# UNG8077_EVB_7801-9031_A_5-Power.net
KiCad netlist of a schematic drawn in Altium Designer
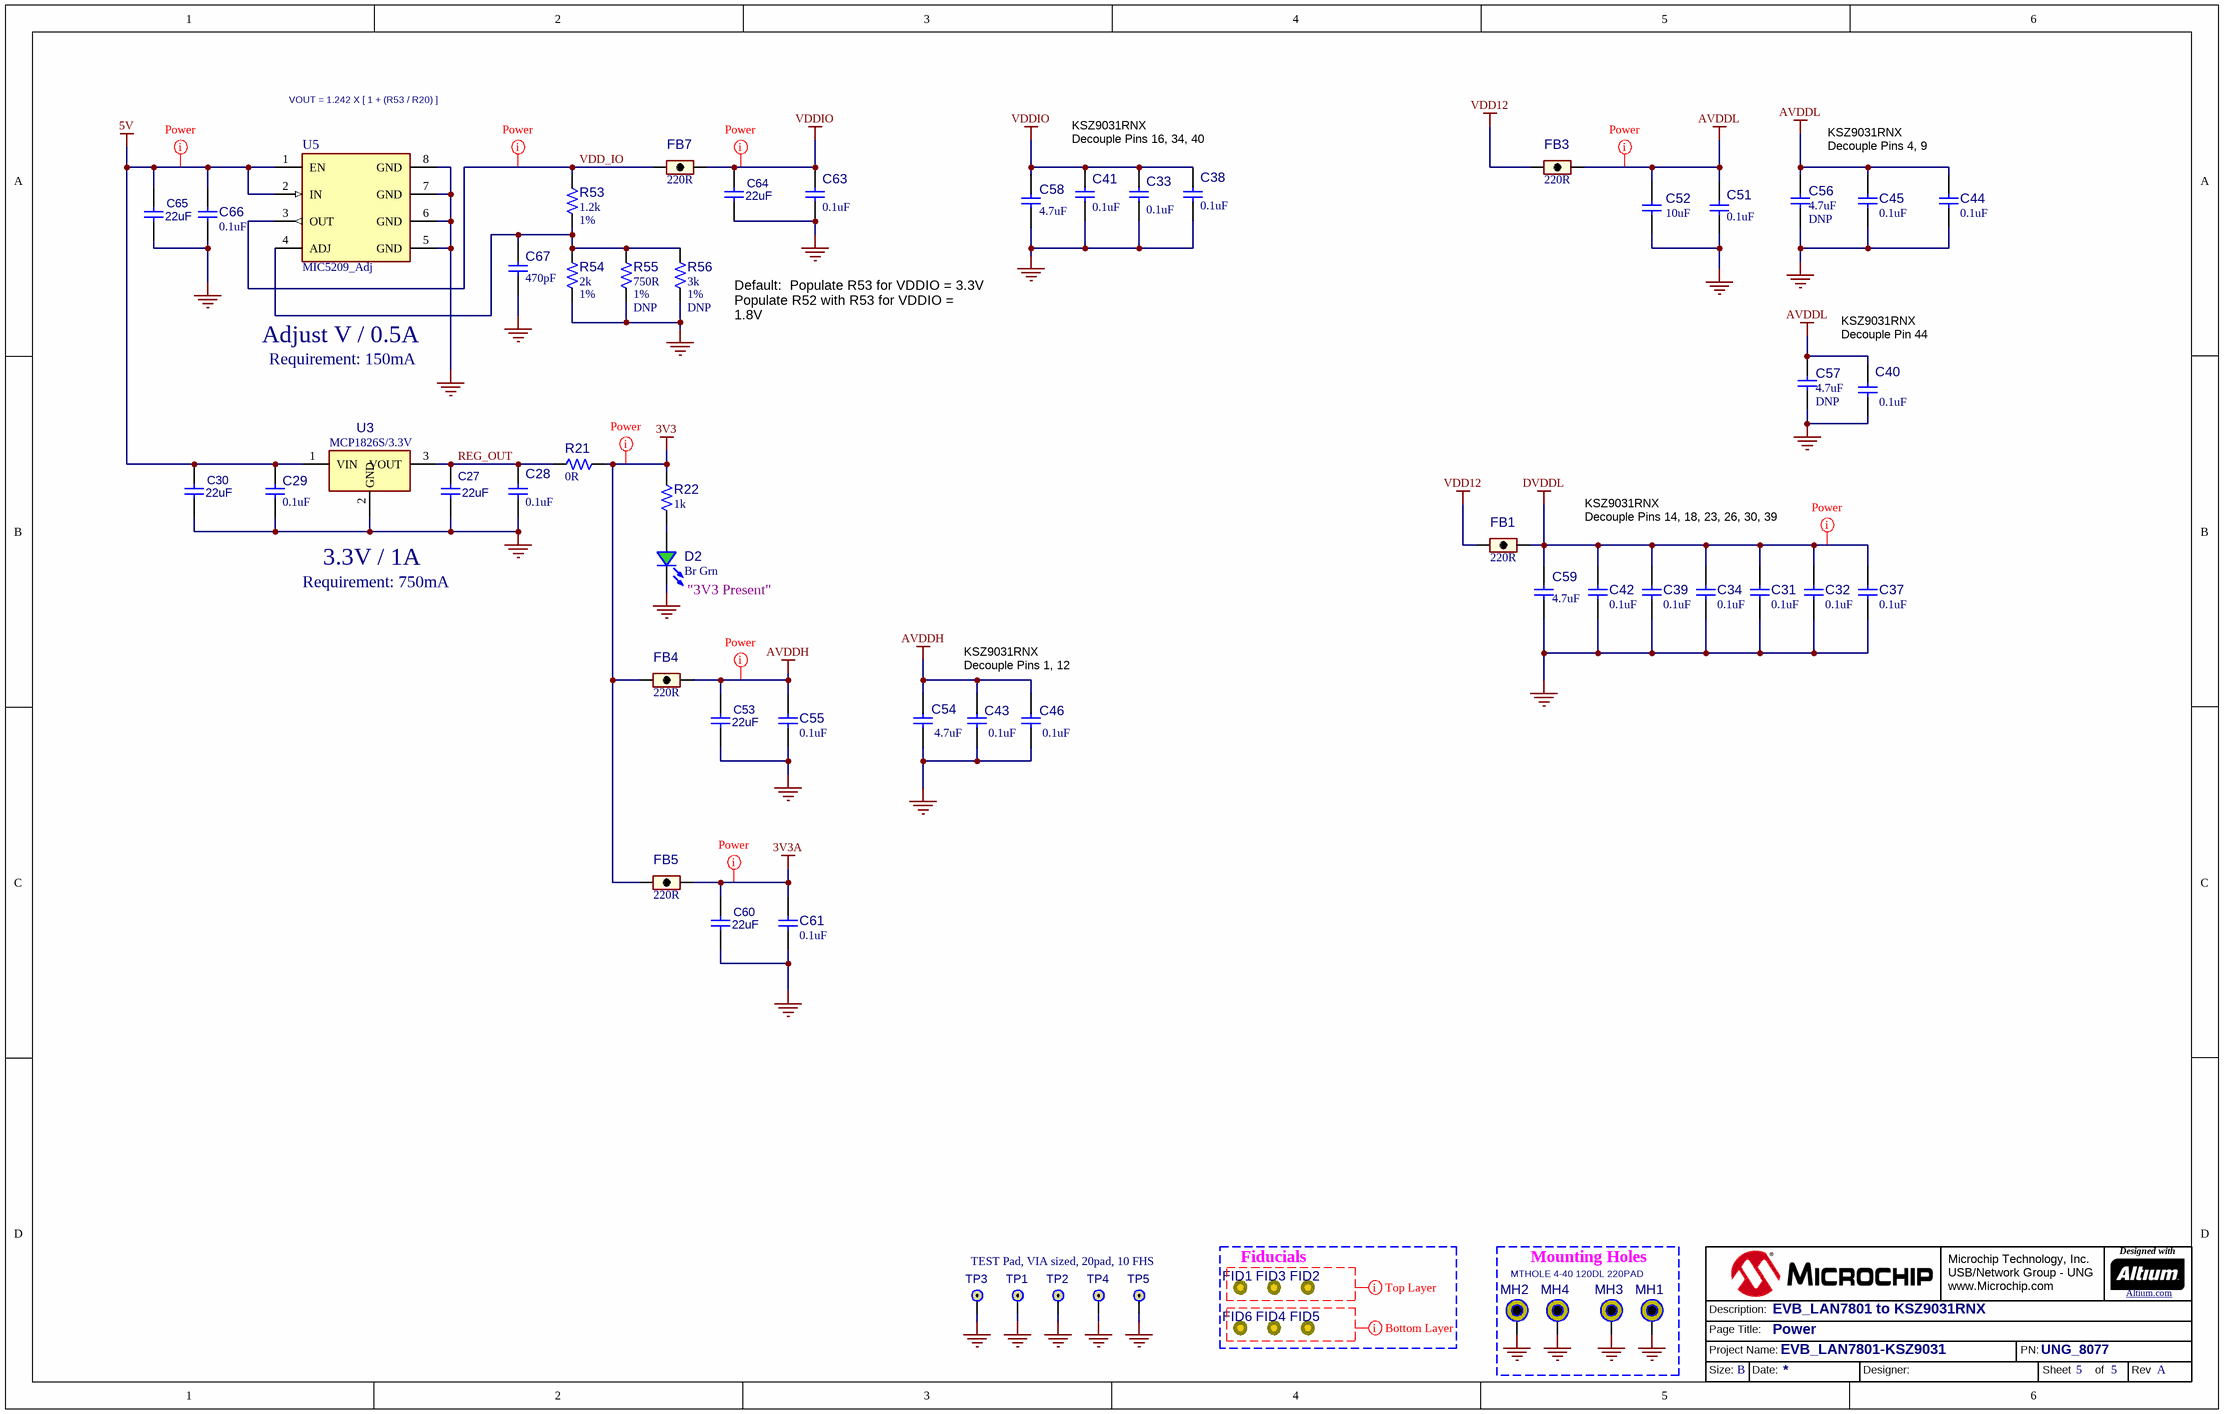
[diagram p0: UNG8077_EVB_7801-9031_A_5-Power.SchDoc]

(export (version "E")
  (design (tool "Eeschema 10.0.6"))
  (components
    (comp (ref "C27")
      (value "22uF")
      (footprint "CAP_C_0805")
      (description "CAP CER 22uF 10V 20% X5R SMD 0805")
      (fields (field (name "TOLERANCE") "20%") (field (name "OWNER") "Jennifer Hancock"))
      (libsource (lib "UNG_CAPACITORS") (part "CAP CER 22uF 10V 20% X5R SMD 0805"))
    )
    (comp (ref "C28")
      (value "0.1uF")
      (footprint "CAP_C_0402")
      (description "Capacitor")
      (fields
        (field (name "TOLERANCE") "10%")
        (field (name "Comment") "CAP CER 0.1UF 35V")
        (field (name "OWNER") "Jamus Griego")
      )
      (libsource (lib "MCHP-CDB-Offline") (part "Capacitor NP"))
    )
    (comp (ref "C29")
      (value "0.1uF")
      (footprint "CAP_C_0402")
      (description "Capacitor")
      (fields
        (field (name "TOLERANCE") "10%")
        (field (name "Comment") "CAP CER 0.1UF 35V")
        (field (name "OWNER") "Jamus Griego")
      )
      (libsource (lib "MCHP-CDB-Offline") (part "Capacitor NP"))
    )
    (comp (ref "C30")
      (value "22uF")
      (footprint "CAP_C_0805")
      (description "CAP CER 22uF 10V 20% X5R SMD 0805")
      (fields (field (name "TOLERANCE") "20%") (field (name "OWNER") "Jennifer Hancock"))
      (libsource (lib "UNG_CAPACITORS") (part "CAP CER 22uF 10V 20% X5R SMD 0805"))
    )
    (comp (ref "C31")
      (value "0.1uF")
      (footprint "CAP_C_0402")
      (description "Capacitor")
      (fields
        (field (name "TOLERANCE") "10%")
        (field (name "Comment") "CAP CER 0.1UF 35V")
        (field (name "OWNER") "Jamus Griego")
      )
      (libsource (lib "MCHP-CDB-Offline") (part "Capacitor NP"))
    )
    (comp (ref "C32")
      (value "0.1uF")
      (footprint "CAP_C_0402")
      (description "Capacitor")
      (fields
        (field (name "TOLERANCE") "10%")
        (field (name "Comment") "CAP CER 0.1UF 35V")
        (field (name "OWNER") "Jamus Griego")
      )
      (libsource (lib "MCHP-CDB-Offline") (part "Capacitor NP"))
    )
    (comp (ref "C33")
      (value "0.1uF")
      (footprint "CAP_C_0402")
      (description "Capacitor")
      (fields
        (field (name "TOLERANCE") "10%")
        (field (name "Comment") "CAP CER 0.1UF 35V")
        (field (name "OWNER") "Jamus Griego")
      )
      (libsource (lib "MCHP-CDB-Offline") (part "Capacitor NP"))
    )
    (comp (ref "C34")
      (value "0.1uF")
      (footprint "CAP_C_0402")
      (description "Capacitor")
      (fields
        (field (name "TOLERANCE") "10%")
        (field (name "Comment") "CAP CER 0.1UF 35V")
        (field (name "OWNER") "Jamus Griego")
      )
      (libsource (lib "MCHP-CDB-Offline") (part "Capacitor NP"))
    )
    (comp (ref "C37")
      (value "0.1uF")
      (footprint "CAP_C_0402")
      (description "Capacitor")
      (fields
        (field (name "TOLERANCE") "10%")
        (field (name "Comment") "CAP CER 0.1UF 35V")
        (field (name "OWNER") "Jamus Griego")
      )
      (libsource (lib "MCHP-CDB-Offline") (part "Capacitor NP"))
    )
    (comp (ref "C38")
      (value "0.1uF")
      (footprint "CAP_C_0402")
      (description "Capacitor")
      (fields
        (field (name "TOLERANCE") "10%")
        (field (name "Comment") "CAP CER 0.1UF 35V")
        (field (name "OWNER") "Jamus Griego")
      )
      (libsource (lib "MCHP-CDB-Offline") (part "Capacitor NP"))
    )
    (comp (ref "C39")
      (value "0.1uF")
      (footprint "CAP_C_0402")
      (description "Capacitor")
      (fields
        (field (name "TOLERANCE") "10%")
        (field (name "Comment") "CAP CER 0.1UF 35V")
        (field (name "OWNER") "Jamus Griego")
      )
      (libsource (lib "MCHP-CDB-Offline") (part "Capacitor NP"))
    )
    (comp (ref "C40")
      (value "0.1uF")
      (footprint "CAP_C_0402")
      (description "Capacitor")
      (fields
        (field (name "TOLERANCE") "10%")
        (field (name "Comment") "CAP CER 0.1UF 35V")
        (field (name "OWNER") "Jamus Griego")
      )
      (libsource (lib "MCHP-CDB-Offline") (part "Capacitor NP"))
    )
    (comp (ref "C41")
      (value "0.1uF")
      (footprint "CAP_C_0402")
      (description "Capacitor")
      (fields
        (field (name "TOLERANCE") "10%")
        (field (name "Comment") "CAP CER 0.1UF 35V")
        (field (name "OWNER") "Jamus Griego")
      )
      (libsource (lib "MCHP-CDB-Offline") (part "Capacitor NP"))
    )
    (comp (ref "C42")
      (value "0.1uF")
      (footprint "CAP_C_0402")
      (description "Capacitor")
      (fields
        (field (name "TOLERANCE") "10%")
        (field (name "Comment") "CAP CER 0.1UF 35V")
        (field (name "OWNER") "Jamus Griego")
      )
      (libsource (lib "MCHP-CDB-Offline") (part "Capacitor NP"))
    )
    (comp (ref "C43")
      (value "0.1uF")
      (footprint "CAP_C_0402")
      (description "Capacitor")
      (fields
        (field (name "TOLERANCE") "10%")
        (field (name "Comment") "CAP CER 0.1UF 35V")
        (field (name "OWNER") "Jamus Griego")
      )
      (libsource (lib "MCHP-CDB-Offline") (part "Capacitor NP"))
    )
    (comp (ref "C44")
      (value "0.1uF")
      (footprint "CAP_C_0402")
      (description "Capacitor")
      (fields
        (field (name "TOLERANCE") "10%")
        (field (name "Comment") "CAP CER 0.1UF 35V")
        (field (name "OWNER") "Jamus Griego")
      )
      (libsource (lib "MCHP-CDB-Offline") (part "Capacitor NP"))
    )
    (comp (ref "C45")
      (value "0.1uF")
      (footprint "CAP_C_0402")
      (description "Capacitor")
      (fields
        (field (name "TOLERANCE") "10%")
        (field (name "Comment") "CAP CER 0.1UF 35V")
        (field (name "OWNER") "Jamus Griego")
      )
      (libsource (lib "MCHP-CDB-Offline") (part "Capacitor NP"))
    )
    (comp (ref "C46")
      (value "0.1uF")
      (footprint "CAP_C_0402")
      (description "Capacitor")
      (fields
        (field (name "TOLERANCE") "10%")
        (field (name "Comment") "CAP CER 0.1UF 35V")
        (field (name "OWNER") "Jamus Griego")
      )
      (libsource (lib "MCHP-CDB-Offline") (part "Capacitor NP"))
    )
    (comp (ref "C51")
      (value "0.1uF")
      (footprint "CAP_C_0402")
      (description "Capacitor")
      (fields
        (field (name "TOLERANCE") "10%")
        (field (name "Comment") "CAP CER 0.1UF 35V")
        (field (name "OWNER") "Jamus Griego")
      )
      (libsource (lib "MCHP-CDB-Offline") (part "Capacitor NP"))
    )
    (comp (ref "C52")
      (value "10uF")
      (footprint "CAP_C_0603")
      (description "Capacitor")
      (fields (field (name "TOLERANCE") "20%") (field (name "Comment") "Capacitor NP"))
      (libsource (lib "MCHP-CDB-Offline") (part "Capacitor NP"))
    )
    (comp (ref "C53")
      (value "22uF")
      (footprint "CAP_C_0805")
      (description "CAP CER 22uF 10V 20% X5R SMD 0805")
      (fields (field (name "TOLERANCE") "20%") (field (name "OWNER") "Jennifer Hancock"))
      (libsource (lib "UNG_CAPACITORS") (part "CAP CER 22uF 10V 20% X5R SMD 0805"))
    )
    (comp (ref "C54")
      (value "4.7uF")
      (footprint "CAP_C_0603")
      (description "Capacitor")
      (fields (field (name "TOLERANCE") "20%") (field (name "Comment") "Capacitor NP"))
      (libsource (lib "MCHP-CDB-Offline") (part "Capacitor NP"))
    )
    (comp (ref "C55")
      (value "0.1uF")
      (footprint "CAP_C_0402")
      (description "Capacitor")
      (fields
        (field (name "TOLERANCE") "10%")
        (field (name "Comment") "CAP CER 0.1UF 35V")
        (field (name "OWNER") "Jamus Griego")
      )
      (libsource (lib "MCHP-CDB-Offline") (part "Capacitor NP"))
    )
    (comp (ref "C56")
      (value "4.7uF")
      (footprint "CAP_C_0603")
      (description "Capacitor")
      (fields
        (field (name "TOLERANCE") "20%")
        (field (name "POPULATED") "DNP")
        (field (name "Comment") "Capacitor NP")
      )
      (libsource (lib "MCHP-CDB-Offline") (part "Capacitor NP"))
    )
    (comp (ref "C57")
      (value "4.7uF")
      (footprint "CAP_C_0603")
      (description "Capacitor")
      (fields
        (field (name "TOLERANCE") "20%")
        (field (name "POPULATED") "DNP")
        (field (name "Comment") "Capacitor NP")
      )
      (libsource (lib "MCHP-CDB-Offline") (part "Capacitor NP"))
    )
    (comp (ref "C58")
      (value "4.7uF")
      (footprint "CAP_C_0603")
      (description "Capacitor")
      (fields (field (name "TOLERANCE") "20%") (field (name "Comment") "Capacitor NP"))
      (libsource (lib "MCHP-CDB-Offline") (part "Capacitor NP"))
    )
    (comp (ref "C59")
      (value "4.7uF")
      (footprint "CAP_C_0603")
      (description "Capacitor")
      (fields (field (name "TOLERANCE") "20%") (field (name "Comment") "Capacitor NP"))
      (libsource (lib "MCHP-CDB-Offline") (part "Capacitor NP"))
    )
    (comp (ref "C60")
      (value "22uF")
      (footprint "CAP_C_0805")
      (description "CAP CER 22uF 10V 20% X5R SMD 0805")
      (fields (field (name "TOLERANCE") "20%") (field (name "OWNER") "Jennifer Hancock"))
      (libsource (lib "UNG_CAPACITORS") (part "CAP CER 22uF 10V 20% X5R SMD 0805"))
    )
    (comp (ref "C61")
      (value "0.1uF")
      (footprint "CAP_C_0402")
      (description "Capacitor")
      (fields
        (field (name "TOLERANCE") "10%")
        (field (name "Comment") "CAP CER 0.1UF 35V")
        (field (name "OWNER") "Jamus Griego")
      )
      (libsource (lib "MCHP-CDB-Offline") (part "Capacitor NP"))
    )
    (comp (ref "C63")
      (value "0.1uF")
      (footprint "CAP_C_0402")
      (description "Capacitor")
      (fields
        (field (name "TOLERANCE") "10%")
        (field (name "Comment") "CAP CER 0.1UF 35V")
        (field (name "OWNER") "Jamus Griego")
      )
      (libsource (lib "MCHP-CDB-Offline") (part "Capacitor NP"))
    )
    (comp (ref "C64")
      (value "22uF")
      (footprint "CAP_C_0805")
      (description "CAP CER 22uF 10V 20% X5R SMD 0805")
      (fields (field (name "TOLERANCE") "20%") (field (name "OWNER") "Jennifer Hancock"))
      (libsource (lib "UNG_CAPACITORS") (part "CAP CER 22uF 10V 20% X5R SMD 0805"))
    )
    (comp (ref "C65")
      (value "22uF")
      (footprint "CAP_C_0805")
      (description "CAP CER 22uF 10V 20% X5R SMD 0805")
      (fields (field (name "TOLERANCE") "20%") (field (name "OWNER") "Jennifer Hancock"))
      (libsource (lib "UNG_CAPACITORS") (part "CAP CER 22uF 10V 20% X5R SMD 0805"))
    )
    (comp (ref "C66")
      (value "0.1uF")
      (footprint "CAP_C_0402")
      (description "Capacitor")
      (fields
        (field (name "TOLERANCE") "10%")
        (field (name "Comment") "CAP CER 0.1UF 35V")
        (field (name "OWNER") "Jamus Griego")
      )
      (libsource (lib "MCHP-CDB-Offline") (part "Capacitor NP"))
    )
    (comp (ref "C67")
      (value "470pF")
      (footprint "CAP_C_0402")
      (description "Capacitor")
      (fields
        (field (name "TOLERANCE") "5%")
        (field (name "Comment") "Capacitor NP")
        (field (name "OWNER") "Duane Burt")
      )
      (libsource (lib "MCHP-CDB-Offline") (part "Capacitor NP"))
    )
    (comp (ref "D2")
      (value "Br Grn")
      (footprint "LED_0603_GREEN")
      (description "LED, Bright Green, 0603")
      (fields (field (name "Comment") "LED") (field (name "OWNER") "Jennifer Hancock"))
      (libsource (lib "UNG_DIODES") (part "LED, Bright Green, 0603"))
    )
    (comp (ref "FB1")
      (value "220R")
      (footprint "IND_C_0603")
      (fields (field (name "Comment") "Ferrite Bead") (field (name "OWNER") "Razvan Cristescu"))
      (libsource (lib "MCHP-CDB-Offline") (part "Ferrite Bead"))
    )
    (comp (ref "FB3")
      (value "220R")
      (footprint "IND_C_0603")
      (fields (field (name "Comment") "Ferrite Bead") (field (name "OWNER") "Razvan Cristescu"))
      (libsource (lib "MCHP-CDB-Offline") (part "Ferrite Bead"))
    )
    (comp (ref "FB4")
      (value "220R")
      (footprint "IND_C_0603")
      (fields (field (name "Comment") "Ferrite Bead") (field (name "OWNER") "Razvan Cristescu"))
      (libsource (lib "MCHP-CDB-Offline") (part "Ferrite Bead"))
    )
    (comp (ref "FB5")
      (value "220R")
      (footprint "IND_C_0603")
      (fields (field (name "Comment") "Ferrite Bead") (field (name "OWNER") "Razvan Cristescu"))
      (libsource (lib "MCHP-CDB-Offline") (part "Ferrite Bead"))
    )
    (comp (ref "FB7")
      (value "220R")
      (footprint "IND_C_0603")
      (fields (field (name "Comment") "Ferrite Bead") (field (name "OWNER") "Razvan Cristescu"))
      (libsource (lib "MCHP-CDB-Offline") (part "Ferrite Bead"))
    )
    (comp (ref "FID1")
      (value "FIDUCIAL")
      (footprint "FIDUCIAL")
      (libsource (lib "UNG_MISC") (part "FIDUCIAL"))
    )
    (comp (ref "FID2")
      (value "FIDUCIAL")
      (footprint "FIDUCIAL")
      (libsource (lib "UNG_MISC") (part "FIDUCIAL"))
    )
    (comp (ref "FID3")
      (value "FIDUCIAL")
      (footprint "FIDUCIAL")
      (libsource (lib "UNG_MISC") (part "FIDUCIAL"))
    )
    (comp (ref "FID4")
      (value "FIDUCIAL")
      (footprint "FIDUCIAL")
      (libsource (lib "UNG_MISC") (part "FIDUCIAL"))
    )
    (comp (ref "FID5")
      (value "FIDUCIAL")
      (footprint "FIDUCIAL")
      (libsource (lib "UNG_MISC") (part "FIDUCIAL"))
    )
    (comp (ref "FID6")
      (value "FIDUCIAL")
      (footprint "FIDUCIAL")
      (libsource (lib "UNG_MISC") (part "FIDUCIAL"))
    )
    (comp (ref "MH1")
      (value "MTHOLE 4-40 120DL 220PAD")
      (footprint "MTHOLE_4-40")
      (libsource (lib "UNG_MISC") (part "MTHOLE 4-40 120DL 220PAD"))
    )
    (comp (ref "MH2")
      (value "MTHOLE 4-40 120DL 220PAD")
      (footprint "MTHOLE_4-40")
      (libsource (lib "UNG_MISC") (part "MTHOLE 4-40 120DL 220PAD"))
    )
    (comp (ref "MH3")
      (value "MTHOLE 4-40 120DL 220PAD")
      (footprint "MTHOLE_4-40")
      (libsource (lib "UNG_MISC") (part "MTHOLE 4-40 120DL 220PAD"))
    )
    (comp (ref "MH4")
      (value "MTHOLE 4-40 120DL 220PAD")
      (footprint "MTHOLE_4-40")
      (libsource (lib "UNG_MISC") (part "MTHOLE 4-40 120DL 220PAD"))
    )
    (comp (ref "R21")
      (value "0R")
      (footprint "RES_C_0603")
      (description "Resistor")
      (fields (field (name "POWER") "1/10W"))
      (libsource (lib "MCHP-CDB-Offline") (part "Resistor"))
    )
    (comp (ref "R22")
      (value "1k")
      (footprint "RES_C_0603")
      (description "Resistor")
      (fields (field (name "TOLERANCE") "1%") (field (name "VOLTAGE") "75V"))
      (libsource (lib "MCHP-CDB") (part "Resistor"))
    )
    (comp (ref "R53")
      (value "1.2k")
      (footprint "RES_C_0603")
      (description "Resistor")
      (fields
        (field (name "TOLERANCE") "1%")
        (field (name "VOLTAGE") "50V")
        (field (name "POWER") "1/10W")
        (field (name "OWNER") "Aaron VanDuerm")
      )
      (libsource (lib "MCHP-CDB-Offline") (part "Resistor"))
    )
    (comp (ref "R54")
      (value "2k")
      (footprint "RES_C_0603")
      (description "Resistor")
      (fields (field (name "TOLERANCE") "1%") (field (name "VOLTAGE") "75V") (field (name "POWER") "1/10W"))
      (libsource (lib "MCHP-CDB-Offline") (part "Resistor"))
    )
    (comp (ref "R55")
      (value "750R")
      (footprint "RES_C_0603")
      (description "Resistor")
      (fields
        (field (name "TOLERANCE") "1%")
        (field (name "VOLTAGE") "75V")
        (field (name "POWER") "1/10W")
        (field (name "POPULATED") "DNP")
        (field (name "OWNER") "Tad Ahlvers")
      )
      (libsource (lib "MCHP-CDB-Offline") (part "Resistor"))
    )
    (comp (ref "R56")
      (value "3k")
      (footprint "RES_C_0603")
      (description "Resistor")
      (fields
        (field (name "TOLERANCE") "1%")
        (field (name "VOLTAGE") "75V")
        (field (name "POWER") "1/10W")
        (field (name "POPULATED") "DNP")
        (field (name "OWNER") "Bogdan P (M91398)")
      )
      (libsource (lib "MCHP-CDB-Offline") (part "Resistor"))
    )
    (comp (ref "TP1")
      (value "Jumper")
      (footprint "TP_PAD_VIA_20-10")
      (description "Test Pad TH VIA 20X10")
      (fields (field (name "MANUFACTURER PART NUMBER") "none"))
      (libsource (lib "UNG_CONNECTORS") (part "TEST PAD TH VIA 20X10"))
    )
    (comp (ref "TP2")
      (value "Jumper")
      (footprint "TP_PAD_VIA_20-10")
      (description "Test Pad TH VIA 20X10")
      (fields (field (name "MANUFACTURER PART NUMBER") "none"))
      (libsource (lib "UNG_CONNECTORS") (part "TEST PAD TH VIA 20X10"))
    )
    (comp (ref "TP3")
      (value "Jumper")
      (footprint "TP_PAD_VIA_20-10")
      (description "Test Pad TH VIA 20X10")
      (fields (field (name "MANUFACTURER PART NUMBER") "none"))
      (libsource (lib "UNG_CONNECTORS") (part "TEST PAD TH VIA 20X10"))
    )
    (comp (ref "TP4")
      (value "Jumper")
      (footprint "TP_PAD_VIA_20-10")
      (description "Test Pad TH VIA 20X10")
      (fields (field (name "MANUFACTURER PART NUMBER") "none"))
      (libsource (lib "UNG_CONNECTORS") (part "TEST PAD TH VIA 20X10"))
    )
    (comp (ref "TP5")
      (value "Jumper")
      (footprint "TP_PAD_VIA_20-10")
      (description "Test Pad TH VIA 20X10")
      (fields
        (field (name "MANUFACTURER PART NUMBER") "none")
        (field (name "DESCRIPTION_") "TEST Pad, VIA sized, 20pad, 10 FHS")
      )
      (libsource (lib "UNG_CONNECTORS") (part "TEST PAD TH VIA 20X10"))
    )
    (comp (ref "U3")
      (value "MCP1826S/3.3V")
      (footprint "SOT-223-3")
      (description "LDO")
      (fields
        (field (name "Comment") "MCP182XS SOT-223-3_DDPAK-3_TO-220-3")
        (field (name "OWNER") "Aaron VanDuerm")
      )
      (libsource (lib "MCHP-CDB-Offline") (part "MCP182XS SOT-223-3_DDPAK-3_TO-220-3"))
    )
    (comp (ref "U5")
      (value "MIC5209_Adj")
      (footprint "SOIC-8")
      (description "LDO MIC5209")
      (fields (field (name "Comment") "MIC5209 ADJ SOIC-8"))
      (libsource (lib "MCHP-CDB") (part "MIC5209 ADJ SOIC-8"))
    )
  )
  (nets
    (net (code "1") (name "/REG_OUT") (class "Default")
      (node (ref "C27") (pin "2") (pinfunction "2_2") (pintype "passive"))
      (node (ref "C28") (pin "2") (pinfunction "2_2") (pintype "passive"))
      (node (ref "R21") (pin "1") (pinfunction "1_1") (pintype "passive"))
      (node (ref "U3") (pin "3") (pinfunction "VOUT_3") (pintype "power_in"))
    )
    (net (code "2") (name "/VDD_IO") (class "Default")
      (node (ref "FB7") (pin "1") (pinfunction "1_1") (pintype "passive"))
      (node (ref "R53") (pin "2") (pinfunction "2_2") (pintype "passive"))
      (node (ref "U5") (pin "3") (pinfunction "OUT_3") (pintype "output"))
    )
    (net (code "3") (name "3V3") (class "Default")
      (node (ref "FB4") (pin "1") (pinfunction "1_1") (pintype "passive"))
      (node (ref "FB5") (pin "1") (pinfunction "1_1") (pintype "passive"))
      (node (ref "R21") (pin "2") (pinfunction "2_2") (pintype "passive"))
      (node (ref "R22") (pin "1") (pinfunction "1_1") (pintype "passive"))
    )
    (net (code "4") (name "3V3A") (class "Default")
      (node (ref "C60") (pin "2") (pinfunction "2_2") (pintype "passive"))
      (node (ref "C61") (pin "2") (pinfunction "2_2") (pintype "passive"))
      (node (ref "FB5") (pin "2") (pinfunction "2_2") (pintype "passive"))
    )
    (net (code "5") (name "5V") (class "Default")
      (node (ref "C29") (pin "2") (pinfunction "2_2") (pintype "passive"))
      (node (ref "C30") (pin "2") (pinfunction "2_2") (pintype "passive"))
      (node (ref "C65") (pin "2") (pinfunction "2_2") (pintype "passive"))
      (node (ref "C66") (pin "2") (pinfunction "2_2") (pintype "passive"))
      (node (ref "U3") (pin "1") (pinfunction "VIN_1") (pintype "power_in"))
      (node (ref "U5") (pin "1") (pinfunction "EN_1") (pintype "passive"))
      (node (ref "U5") (pin "2") (pinfunction "IN_2") (pintype "input"))
    )
    (net (code "6") (name "AVDDH") (class "Default")
      (node (ref "C43") (pin "2") (pinfunction "2_2") (pintype "passive"))
      (node (ref "C46") (pin "2") (pinfunction "2_2") (pintype "passive"))
      (node (ref "C53") (pin "2") (pinfunction "2_2") (pintype "passive"))
      (node (ref "C54") (pin "2") (pinfunction "2_2") (pintype "passive"))
      (node (ref "C55") (pin "2") (pinfunction "2_2") (pintype "passive"))
      (node (ref "FB4") (pin "2") (pinfunction "2_2") (pintype "passive"))
    )
    (net (code "7") (name "AVDDL") (class "Default")
      (node (ref "C40") (pin "2") (pinfunction "2_2") (pintype "passive"))
      (node (ref "C44") (pin "2") (pinfunction "2_2") (pintype "passive"))
      (node (ref "C45") (pin "2") (pinfunction "2_2") (pintype "passive"))
      (node (ref "C51") (pin "2") (pinfunction "2_2") (pintype "passive"))
      (node (ref "C52") (pin "2") (pinfunction "2_2") (pintype "passive"))
      (node (ref "C56") (pin "2") (pinfunction "2_2") (pintype "passive"))
      (node (ref "C57") (pin "2") (pinfunction "2_2") (pintype "passive"))
      (node (ref "FB3") (pin "2") (pinfunction "2_2") (pintype "passive"))
    )
    (net (code "8") (name "DVDDL") (class "Default")
      (node (ref "C31") (pin "2") (pinfunction "2_2") (pintype "passive"))
      (node (ref "C32") (pin "2") (pinfunction "2_2") (pintype "passive"))
      (node (ref "C34") (pin "2") (pinfunction "2_2") (pintype "passive"))
      (node (ref "C37") (pin "2") (pinfunction "2_2") (pintype "passive"))
      (node (ref "C39") (pin "2") (pinfunction "2_2") (pintype "passive"))
      (node (ref "C42") (pin "2") (pinfunction "2_2") (pintype "passive"))
      (node (ref "C59") (pin "2") (pinfunction "2_2") (pintype "passive"))
      (node (ref "FB1") (pin "2") (pinfunction "2_2") (pintype "passive"))
    )
    (net (code "9") (name "GND") (class "Default")
      (node (ref "C27") (pin "1") (pinfunction "1_1") (pintype "passive"))
      (node (ref "C28") (pin "1") (pinfunction "1_1") (pintype "passive"))
      (node (ref "C29") (pin "1") (pinfunction "1_1") (pintype "passive"))
      (node (ref "C30") (pin "1") (pinfunction "1_1") (pintype "passive"))
      (node (ref "C31") (pin "1") (pinfunction "1_1") (pintype "passive"))
      (node (ref "C32") (pin "1") (pinfunction "1_1") (pintype "passive"))
      (node (ref "C33") (pin "1") (pinfunction "1_1") (pintype "passive"))
      (node (ref "C34") (pin "1") (pinfunction "1_1") (pintype "passive"))
      (node (ref "C37") (pin "1") (pinfunction "1_1") (pintype "passive"))
      (node (ref "C38") (pin "1") (pinfunction "1_1") (pintype "passive"))
      (node (ref "C39") (pin "1") (pinfunction "1_1") (pintype "passive"))
      (node (ref "C40") (pin "1") (pinfunction "1_1") (pintype "passive"))
      (node (ref "C41") (pin "1") (pinfunction "1_1") (pintype "passive"))
      (node (ref "C42") (pin "1") (pinfunction "1_1") (pintype "passive"))
      (node (ref "C43") (pin "1") (pinfunction "1_1") (pintype "passive"))
      (node (ref "C44") (pin "1") (pinfunction "1_1") (pintype "passive"))
      (node (ref "C45") (pin "1") (pinfunction "1_1") (pintype "passive"))
      (node (ref "C46") (pin "1") (pinfunction "1_1") (pintype "passive"))
      (node (ref "C51") (pin "1") (pinfunction "1_1") (pintype "passive"))
      (node (ref "C52") (pin "1") (pinfunction "1_1") (pintype "passive"))
      (node (ref "C53") (pin "1") (pinfunction "1_1") (pintype "passive"))
      (node (ref "C54") (pin "1") (pinfunction "1_1") (pintype "passive"))
      (node (ref "C55") (pin "1") (pinfunction "1_1") (pintype "passive"))
      (node (ref "C56") (pin "1") (pinfunction "1_1") (pintype "passive"))
      (node (ref "C57") (pin "1") (pinfunction "1_1") (pintype "passive"))
      (node (ref "C58") (pin "1") (pinfunction "1_1") (pintype "passive"))
      (node (ref "C59") (pin "1") (pinfunction "1_1") (pintype "passive"))
      (node (ref "C60") (pin "1") (pinfunction "1_1") (pintype "passive"))
      (node (ref "C61") (pin "1") (pinfunction "1_1") (pintype "passive"))
      (node (ref "C63") (pin "1") (pinfunction "1_1") (pintype "passive"))
      (node (ref "C64") (pin "1") (pinfunction "1_1") (pintype "passive"))
      (node (ref "C65") (pin "1") (pinfunction "1_1") (pintype "passive"))
      (node (ref "C66") (pin "1") (pinfunction "1_1") (pintype "passive"))
      (node (ref "C67") (pin "1") (pinfunction "1_1") (pintype "passive"))
      (node (ref "D2") (pin "2") (pinfunction "K_2") (pintype "passive"))
      (node (ref "MH1") (pin "1") (pinfunction "1_1") (pintype "passive"))
      (node (ref "MH2") (pin "1") (pinfunction "1_1") (pintype "passive"))
      (node (ref "MH3") (pin "1") (pinfunction "1_1") (pintype "passive"))
      (node (ref "MH4") (pin "1") (pinfunction "1_1") (pintype "passive"))
      (node (ref "R54") (pin "1") (pinfunction "1_1") (pintype "passive"))
      (node (ref "R55") (pin "1") (pinfunction "1_1") (pintype "passive"))
      (node (ref "R56") (pin "1") (pinfunction "1_1") (pintype "passive"))
      (node (ref "TP1") (pin "1") (pinfunction "P1_1") (pintype "passive"))
      (node (ref "TP2") (pin "1") (pinfunction "P1_1") (pintype "passive"))
      (node (ref "TP3") (pin "1") (pinfunction "P1_1") (pintype "passive"))
      (node (ref "TP4") (pin "1") (pinfunction "P1_1") (pintype "passive"))
      (node (ref "TP5") (pin "1") (pinfunction "P1_1") (pintype "passive"))
      (node (ref "U3") (pin "2") (pinfunction "GND_2") (pintype "power_in"))
      (node (ref "U5") (pin "5") (pinfunction "GND_5") (pintype "power_in"))
      (node (ref "U5") (pin "6") (pinfunction "GND_6") (pintype "passive"))
      (node (ref "U5") (pin "7") (pinfunction "GND_7") (pintype "passive"))
      (node (ref "U5") (pin "8") (pinfunction "GND_8") (pintype "power_in"))
    )
    (net (code "10") (name "Net-(D2-A)") (class "Default")
      (node (ref "D2") (pin "1") (pinfunction "A_1") (pintype "passive"))
      (node (ref "R22") (pin "2") (pinfunction "2_2") (pintype "passive"))
    )
    (net (code "11") (name "Net-(U5-ADJ)") (class "Default")
      (node (ref "C67") (pin "2") (pinfunction "2_2") (pintype "passive"))
      (node (ref "R53") (pin "1") (pinfunction "1_1") (pintype "passive"))
      (node (ref "R54") (pin "2") (pinfunction "2_2") (pintype "passive"))
      (node (ref "R55") (pin "2") (pinfunction "2_2") (pintype "passive"))
      (node (ref "R56") (pin "2") (pinfunction "2_2") (pintype "passive"))
      (node (ref "U5") (pin "4") (pinfunction "ADJ_4") (pintype "passive"))
    )
    (net (code "12") (name "VDD12") (class "Default")
      (node (ref "FB1") (pin "1") (pinfunction "1_1") (pintype "passive"))
      (node (ref "FB3") (pin "1") (pinfunction "1_1") (pintype "passive"))
    )
    (net (code "13") (name "VDDIO") (class "Default")
      (node (ref "C33") (pin "2") (pinfunction "2_2") (pintype "passive"))
      (node (ref "C38") (pin "2") (pinfunction "2_2") (pintype "passive"))
      (node (ref "C41") (pin "2") (pinfunction "2_2") (pintype "passive"))
      (node (ref "C58") (pin "2") (pinfunction "2_2") (pintype "passive"))
      (node (ref "C63") (pin "2") (pinfunction "2_2") (pintype "passive"))
      (node (ref "C64") (pin "2") (pinfunction "2_2") (pintype "passive"))
      (node (ref "FB7") (pin "2") (pinfunction "2_2") (pintype "passive"))
    )
  )
)
